# Alimentation_USB_Header.net
KiCad netlist of a schematic drawn in Altium Designer
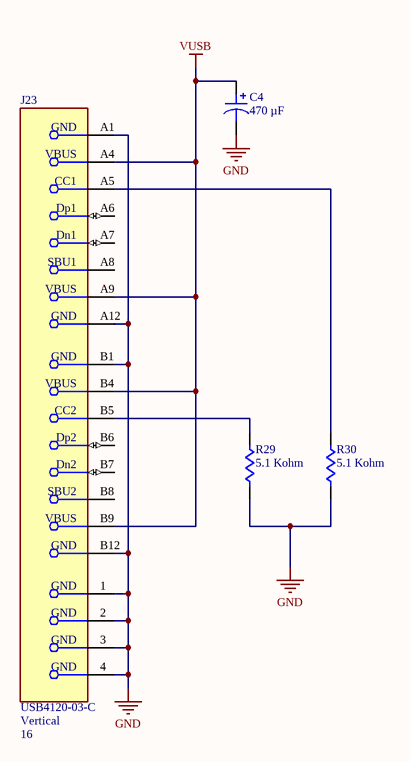
[diagram p0: Alimentation_USB_Header.SchDoc]

(export (version "E")
  (design (tool "Eeschema 10.0.6"))
  (components
    (comp (ref "C4")
      (value "470 µF")
      (footprint "CAP TH ALPOLY D10.00mm S5.00mm H13.00mm")
      (description "CAP ALUM POLY 470UF 20% 25V T/H")
      (fields (field (name "PART NUMBER") "A759MS477M1EAAE020") (field (name "MANUFACTURER") "KEMET"))
      (libsource (lib "Celestial Altium Library - altium_library") (part "Polarised Capacitor"))
    )
    (comp (ref "J23")
      (value "USB4120-03-C")
      (footprint "FP-USB4120-03-C-MFG")
      (description "USB4120-03-C 16 Position 48 VDC USB Type C Vertical USB 2.0 Receptacle Connector")
      (fields (field (name "ORIENTATION") "Vertical") (field (name "NUMBER OF PINS") "16"))
      (libsource (lib "Altium Content Vault") (part "7d1897e331a05e41f957c7eb139585a"))
    )
    (comp (ref "R29")
      (value "5.1 Kohm")
      (footprint "Res_Template")
      (description "Custom Semiconductor Resistor")
      (libsource (lib "Schlib1") (part "470 ohm"))
    )
    (comp (ref "R30")
      (value "5.1 Kohm")
      (footprint "Res_Template")
      (description "Custom Semiconductor Resistor")
      (libsource (lib "Schlib1") (part "470 ohm"))
    )
  )
  (nets
    (net (code "1") (name "GND") (class "Default")
      (node (ref "C4") (pin "2") (pinfunction "2_2") (pintype "passive"))
      (node (ref "J23") (pin "1") (pinfunction "GND_1") (pintype "power_in"))
      (node (ref "J23") (pin "2") (pinfunction "GND_2") (pintype "power_in"))
      (node (ref "J23") (pin "3") (pinfunction "GND_3") (pintype "power_in"))
      (node (ref "J23") (pin "4") (pinfunction "GND_4") (pintype "power_in"))
      (node (ref "J23") (pin "A1") (pinfunction "GND_A1") (pintype "power_in"))
      (node (ref "J23") (pin "A12") (pinfunction "GND_A12") (pintype "power_in"))
      (node (ref "J23") (pin "B1") (pinfunction "GND_B1") (pintype "power_in"))
      (node (ref "J23") (pin "B12") (pinfunction "GND_B12") (pintype "power_in"))
      (node (ref "R29") (pin "1") (pinfunction "1_1") (pintype "passive"))
      (node (ref "R30") (pin "1") (pinfunction "1_1") (pintype "passive"))
    )
    (net (code "2") (name "Net-(J23-CC1)") (class "Default")
      (node (ref "J23") (pin "A5") (pinfunction "CC1_A5") (pintype "passive"))
      (node (ref "R30") (pin "2") (pinfunction "2_2") (pintype "passive"))
    )
    (net (code "3") (name "Net-(J23-CC2)") (class "Default")
      (node (ref "J23") (pin "B5") (pinfunction "CC2_B5") (pintype "passive"))
      (node (ref "R29") (pin "2") (pinfunction "2_2") (pintype "passive"))
    )
    (net (code "4") (name "VUSB") (class "Default")
      (node (ref "C4") (pin "1") (pinfunction "1_1") (pintype "passive"))
      (node (ref "J23") (pin "A4") (pinfunction "VBUS_A4") (pintype "power_in"))
      (node (ref "J23") (pin "A9") (pinfunction "VBUS_A9") (pintype "power_in"))
      (node (ref "J23") (pin "B4") (pinfunction "VBUS_B4") (pintype "power_in"))
      (node (ref "J23") (pin "B9") (pinfunction "VBUS_B9") (pintype "power_in"))
    )
    (net (code "5") (name "unconnected-(J23-Dn1-PadA7)") (class "Default")
      (node (ref "J23") (pin "A7") (pinfunction "Dn1_A7") (pintype "bidirectional"))
    )
    (net (code "6") (name "unconnected-(J23-Dn2-PadB7)") (class "Default")
      (node (ref "J23") (pin "B7") (pinfunction "Dn2_B7") (pintype "bidirectional"))
    )
    (net (code "7") (name "unconnected-(J23-Dp1-PadA6)") (class "Default")
      (node (ref "J23") (pin "A6") (pinfunction "Dp1_A6") (pintype "bidirectional"))
    )
    (net (code "8") (name "unconnected-(J23-Dp2-PadB6)") (class "Default")
      (node (ref "J23") (pin "B6") (pinfunction "Dp2_B6") (pintype "bidirectional"))
    )
    (net (code "9") (name "unconnected-(J23-SBU1-PadA8)") (class "Default")
      (node (ref "J23") (pin "A8") (pinfunction "SBU1_A8") (pintype "passive"))
    )
    (net (code "10") (name "unconnected-(J23-SBU2-PadB8)") (class "Default")
      (node (ref "J23") (pin "B8") (pinfunction "SBU2_B8") (pintype "passive"))
    )
  )
)
